# measurment_synth.net
KiCad netlist of a schematic drawn in Altium Designer
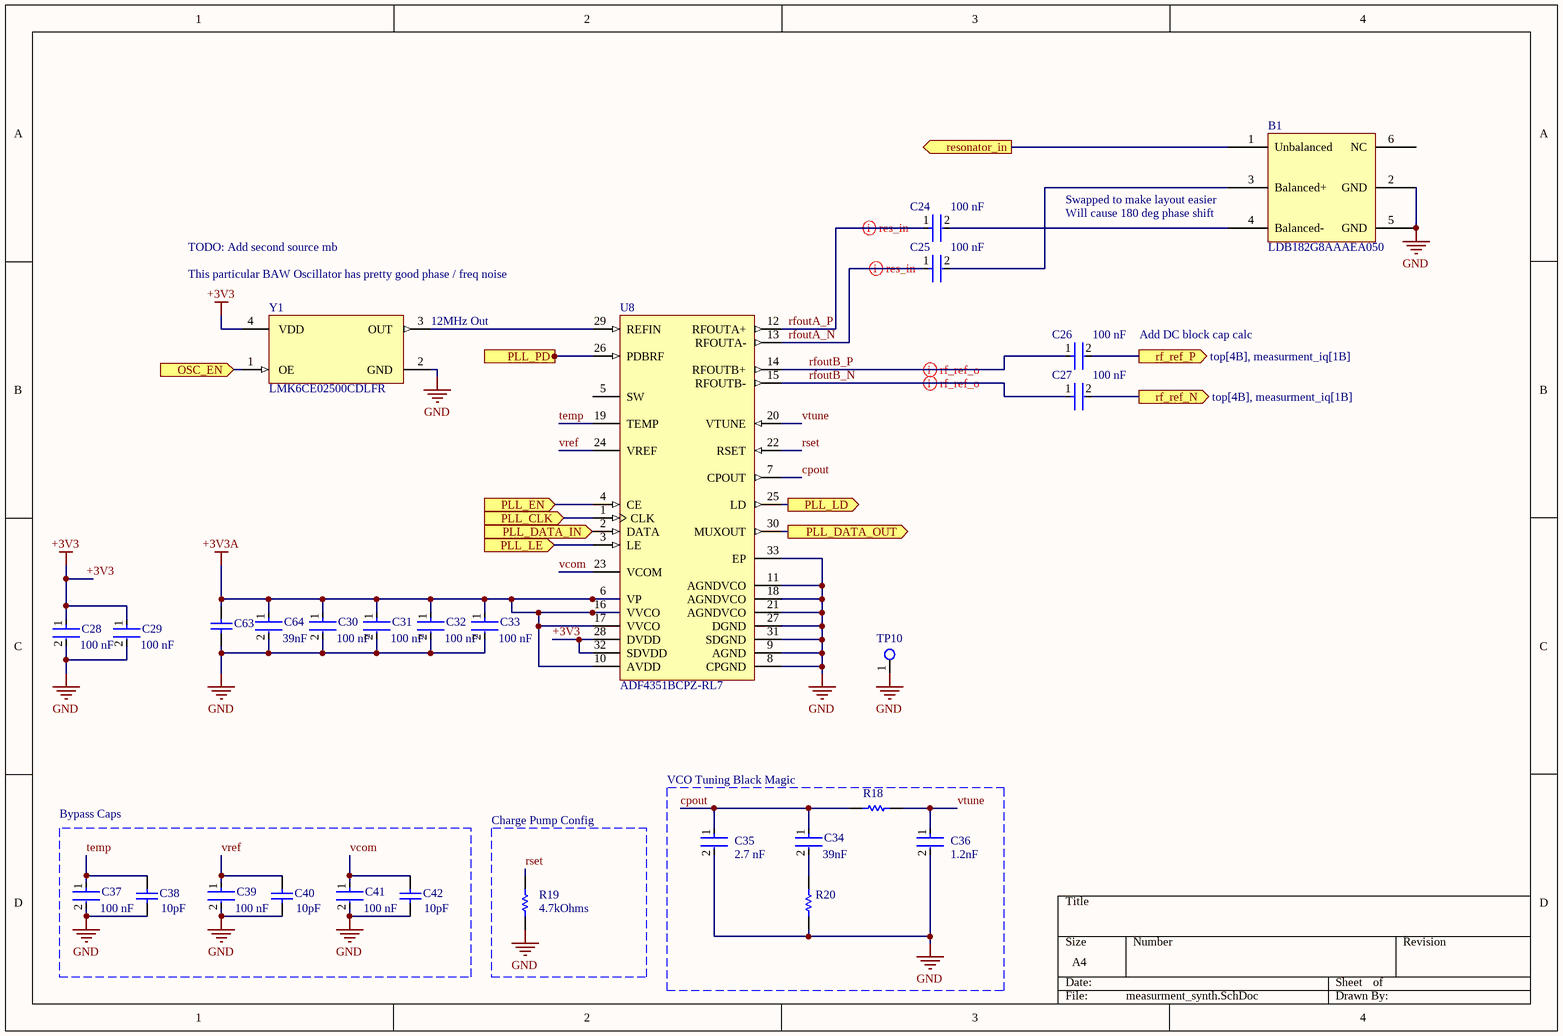
[diagram p0: measurment_synth.SchDoc]

(export (version "E")
  (design (tool "Eeschema 10.0.6"))
  (components
    (comp (ref "B1")
      (value "LDB182G8AAAEA050")
      (footprint "Balum")
      (libsource (lib "fydp") (part "LDB182G8AAAEA050"))
    )
    (comp (ref "C24")
      (value "CC0603KRX7R7BB104")
      (footprint "FP-CC0603-DA-MFG")
      (description "CAP CER 0.1UF 16V X7R 0603")
      (fields
        (field (name "OCTOPART") "https://octopart.com/cc0603krx7r7bb104-yageo-192941")
        (field (name "TOLERANCE") "0.1")
        (field (name "CAPACITANCE") "100 nF")
      )
      (libsource (lib "Altium Content Vault") (part "11868f565c42a9108669ba33697ecf6"))
    )
    (comp (ref "C25")
      (value "CC0603KRX7R7BB104")
      (footprint "FP-CC0603-DA-MFG")
      (description "CAP CER 0.1UF 16V X7R 0603")
      (fields
        (field (name "OCTOPART") "https://octopart.com/cc0603krx7r7bb104-yageo-192941")
        (field (name "TOLERANCE") "0.1")
        (field (name "CAPACITANCE") "100 nF")
      )
      (libsource (lib "Altium Content Vault") (part "11868f565c42a9108669ba33697ecf6"))
    )
    (comp (ref "C26")
      (value "CC0603KRX7R7BB104")
      (footprint "FP-CC0603-DA-MFG")
      (description "CAP CER 0.1UF 16V X7R 0603")
      (fields
        (field (name "OCTOPART") "https://octopart.com/cc0603krx7r7bb104-yageo-192941")
        (field (name "TOLERANCE") "0.1")
        (field (name "CAPACITANCE") "100 nF")
      )
      (libsource (lib "Altium Content Vault") (part "11868f565c42a9108669ba33697ecf6"))
    )
    (comp (ref "C27")
      (value "CC0603KRX7R7BB104")
      (footprint "FP-CC0603-DA-MFG")
      (description "CAP CER 0.1UF 16V X7R 0603")
      (fields
        (field (name "OCTOPART") "https://octopart.com/cc0603krx7r7bb104-yageo-192941")
        (field (name "TOLERANCE") "0.1")
        (field (name "CAPACITANCE") "100 nF")
      )
      (libsource (lib "Altium Content Vault") (part "11868f565c42a9108669ba33697ecf6"))
    )
    (comp (ref "C28")
      (value "CC0603KRX7R7BB104")
      (footprint "FP-CC0603-DA-MFG")
      (description "CAP CER 0.1UF 16V X7R 0603")
      (fields
        (field (name "OCTOPART") "https://octopart.com/cc0603krx7r7bb104-yageo-192941")
        (field (name "TOLERANCE") "0.1")
        (field (name "CAPACITANCE") "100 nF")
      )
      (libsource (lib "Altium Content Vault") (part "11868f565c42a9108669ba33697ecf6"))
    )
    (comp (ref "C29")
      (value "CC0603KRX7R7BB104")
      (footprint "FP-CC0603-DA-MFG")
      (description "CAP CER 0.1UF 16V X7R 0603")
      (fields
        (field (name "OCTOPART") "https://octopart.com/cc0603krx7r7bb104-yageo-192941")
        (field (name "TOLERANCE") "0.1")
        (field (name "CAPACITANCE") "100 nF")
      )
      (libsource (lib "Altium Content Vault") (part "11868f565c42a9108669ba33697ecf6"))
    )
    (comp (ref "C30")
      (value "CC0603KRX7R7BB104")
      (footprint "FP-CC0603-DA-MFG")
      (description "CAP CER 0.1UF 16V X7R 0603")
      (fields
        (field (name "OCTOPART") "https://octopart.com/cc0603krx7r7bb104-yageo-192941")
        (field (name "TOLERANCE") "0.1")
        (field (name "CAPACITANCE") "100 nF")
      )
      (libsource (lib "Altium Content Vault") (part "11868f565c42a9108669ba33697ecf6"))
    )
    (comp (ref "C31")
      (value "CC0603KRX7R7BB104")
      (footprint "FP-CC0603-DA-MFG")
      (description "CAP CER 0.1UF 16V X7R 0603")
      (fields
        (field (name "OCTOPART") "https://octopart.com/cc0603krx7r7bb104-yageo-192941")
        (field (name "TOLERANCE") "0.1")
        (field (name "CAPACITANCE") "100 nF")
      )
      (libsource (lib "Altium Content Vault") (part "11868f565c42a9108669ba33697ecf6"))
    )
    (comp (ref "C32")
      (value "CC0603KRX7R7BB104")
      (footprint "FP-CC0603-DA-MFG")
      (description "CAP CER 0.1UF 16V X7R 0603")
      (fields
        (field (name "OCTOPART") "https://octopart.com/cc0603krx7r7bb104-yageo-192941")
        (field (name "TOLERANCE") "0.1")
        (field (name "CAPACITANCE") "100 nF")
      )
      (libsource (lib "Altium Content Vault") (part "11868f565c42a9108669ba33697ecf6"))
    )
    (comp (ref "C33")
      (value "CC0603KRX7R7BB104")
      (footprint "FP-CC0603-DA-MFG")
      (description "CAP CER 0.1UF 16V X7R 0603")
      (fields
        (field (name "OCTOPART") "https://octopart.com/cc0603krx7r7bb104-yageo-192941")
        (field (name "TOLERANCE") "0.1")
        (field (name "CAPACITANCE") "100 nF")
      )
      (libsource (lib "Altium Content Vault") (part "11868f565c42a9108669ba33697ecf6"))
    )
    (comp (ref "C34")
      (value "GCM155R71C393KA37D")
      (footprint "FP-GCM155-0_05-IPC_B")
      (description "Ceramic Capacitor for Automotive 39nF ±10% 16VDC X7R 0402 Paper T/R")
      (fields (field (name "CAPACITANCE") "39nF") (field (name "TOLERANCE") "10%"))
      (libsource (lib "Altium Content Vault") (part "02cd4be3c70576c341d710602a673aa"))
    )
    (comp (ref "C35")
      (value "CC0402KPX7R9BB272")
      (footprint "FP-CC0402-MFG")
      (description "CC0402 2.7 nF X7R 10.00% 50 V")
      (fields
        (field (name "MANUFACTURER") "YAGEO")
        (field (name "CAPACITANCE") "2.7 nF")
        (field (name "TOLERANCE") "0.1")
      )
      (libsource (lib "Altium Content Vault") (part "11868f565c42a9108669ba33697ecf6"))
    )
    (comp (ref "C36")
      (value "GCM1885C1H122JA16J")
      (footprint "FP-GCM188-0_1-IPC_A")
      (description "Ceramic Capacitor for Automotive 1.2nF  ±5% 50VDC C0G 0603 Paper T/R")
      (fields (field (name "TOLERANCE") "5%") (field (name "CAPACITANCE") "1.2nF"))
      (libsource (lib "Altium Content Vault") (part "02cd4be3c70576c341d710602a673aa"))
    )
    (comp (ref "C37")
      (value "CC0603KRX7R7BB104")
      (footprint "FP-CC0603-DA-MFG")
      (description "CAP CER 0.1UF 16V X7R 0603")
      (fields
        (field (name "OCTOPART") "https://octopart.com/cc0603krx7r7bb104-yageo-192941")
        (field (name "TOLERANCE") "0.1")
        (field (name "CAPACITANCE") "100 nF")
      )
      (libsource (lib "Altium Content Vault") (part "11868f565c42a9108669ba33697ecf6"))
    )
    (comp (ref "C38")
      (value "CC0402JRNPO9BN100")
      (footprint "CAPC1005X55X25ML05T05")
      (description "Chip Capacitor, 10 pF, +/- 5%, 50 V, -55 to 125 degC, 0402 (1005 Metric), RoHS, Tape and Reel")
      (fields
        (field (name "TOLERANCE") "5%")
        (field (name "MANUFACTURER") "Yageo")
        (field (name "CAPACITANCE") "10pF")
      )
      (libsource (lib "Altium Content Vault") (part "CAP-NP-2"))
    )
    (comp (ref "C39")
      (value "CC0603KRX7R7BB104")
      (footprint "FP-CC0603-DA-MFG")
      (description "CAP CER 0.1UF 16V X7R 0603")
      (fields
        (field (name "OCTOPART") "https://octopart.com/cc0603krx7r7bb104-yageo-192941")
        (field (name "TOLERANCE") "0.1")
        (field (name "CAPACITANCE") "100 nF")
      )
      (libsource (lib "Altium Content Vault") (part "11868f565c42a9108669ba33697ecf6"))
    )
    (comp (ref "C40")
      (value "CC0402JRNPO9BN100")
      (footprint "CAPC1005X55X25ML05T05")
      (description "Chip Capacitor, 10 pF, +/- 5%, 50 V, -55 to 125 degC, 0402 (1005 Metric), RoHS, Tape and Reel")
      (fields
        (field (name "TOLERANCE") "5%")
        (field (name "MANUFACTURER") "Yageo")
        (field (name "CAPACITANCE") "10pF")
      )
      (libsource (lib "Altium Content Vault") (part "CAP-NP-2"))
    )
    (comp (ref "C41")
      (value "CC0603KRX7R7BB104")
      (footprint "FP-CC0603-DA-MFG")
      (description "CAP CER 0.1UF 16V X7R 0603")
      (fields
        (field (name "OCTOPART") "https://octopart.com/cc0603krx7r7bb104-yageo-192941")
        (field (name "TOLERANCE") "0.1")
        (field (name "CAPACITANCE") "100 nF")
      )
      (libsource (lib "Altium Content Vault") (part "11868f565c42a9108669ba33697ecf6"))
    )
    (comp (ref "C42")
      (value "CC0402JRNPO9BN100")
      (footprint "CAPC1005X55X25ML05T05")
      (description "Chip Capacitor, 10 pF, +/- 5%, 50 V, -55 to 125 degC, 0402 (1005 Metric), RoHS, Tape and Reel")
      (fields
        (field (name "TOLERANCE") "5%")
        (field (name "MANUFACTURER") "Yageo")
        (field (name "CAPACITANCE") "10pF")
      )
      (libsource (lib "Altium Content Vault") (part "CAP-NP-2"))
    )
    (comp (ref "C63")
      (value "GRM1555C1H270JA01D")
      (footprint "CAPC1005X55X25LL05T10")
      (fields (field (name "MANUFACTURER") "Murata"))
      (libsource (lib "Altium Content Vault") (part "CAP"))
    )
    (comp (ref "C64")
      (value "GCM155R71C393KA37D")
      (footprint "FP-GCM155-0_05-IPC_B")
      (description "Ceramic Capacitor for Automotive 39nF ±10% 16VDC X7R 0402 Paper T/R")
      (fields (field (name "CAPACITANCE") "39nF") (field (name "TOLERANCE") "10%"))
      (libsource (lib "Altium Content Vault") (part "02cd4be3c70576c341d710602a673aa"))
    )
    (comp (ref "R18")
      (value "RC0402JR-07680RL")
      (footprint "RESC1005X40X25LL05T10")
      (fields (field (name "MANUFACTURER") "Yageo / Phycomp"))
      (libsource (lib "Altium Content Vault") (part "RES"))
    )
    (comp (ref "R19")
      (value "RC0603FR-074K7L")
      (footprint "RESC1608X55X25LL10T15")
      (description "Chip Resistor, 4.7 KOhm, +/- 1%, 0.1 W, -55 to 155 degC, 0603 (1608 Metric), RoHS, Tape and Reel")
      (fields
        (field (name "MANUFACTURER") "Yageo")
        (field (name "RESISTANCE") "4.7kOhms")
        (field (name "TOLERANCE") "1%")
      )
      (libsource (lib "Altium Content Vault") (part "RES-2"))
    )
    (comp (ref "R20")
      (value "RC0603JR-07360RL")
      (footprint "RESC1608X55X25ML10T15")
      (fields (field (name "MANUFACTURER") "Yageo"))
      (libsource (lib "Altium Content Vault") (part "RES"))
    )
    (comp (ref "TP10")
      (value "Test Point")
      (footprint "test_point")
      (libsource (lib "fydp") (part "Test Point"))
    )
    (comp (ref "U8")
      (value "ADF4351BCPZ-RL7")
      (footprint "ADI-CP-32-2_L")
      (description "Wideband Synthesizer with Integrated VCO, CP-32-2, Pb-Free, 1500 Reel")
      (libsource (lib "Altium Content Vault") (part "ADI-ADF4351-CP-32-2"))
    )
    (comp (ref "Y1")
      (value "LMK6CE02500CDLFR")
      (footprint "DLF0004A_MFG")
      (description "\"LOW-JITTER, HIGH-PERFORMANCE, BU\" 25 MHz LVCMOS Oscillator 1.8V Enable/Disable 4-VDFN")
      (libsource (lib "Altium Content Vault") (part "b2b2c4fa024628cfd4920a92de059ff"))
    )
  )
  (nets
    (net (code "1") (name "+3V3") (class "Default")
      (node (ref "C28") (pin "1") (pinfunction "1_1") (pintype "passive"))
      (node (ref "C29") (pin "1") (pinfunction "1_1") (pintype "passive"))
      (node (ref "U8") (pin "28") (pinfunction "DVDD_28") (pintype "power_in"))
      (node (ref "U8") (pin "32") (pinfunction "SDVDD_32") (pintype "power_in"))
      (node (ref "Y1") (pin "4") (pinfunction "VDD_4") (pintype "power_in"))
    )
    (net (code "2") (name "+3V3A") (class "Default")
      (node (ref "C30") (pin "1") (pinfunction "1_1") (pintype "passive"))
      (node (ref "C31") (pin "1") (pinfunction "1_1") (pintype "passive"))
      (node (ref "C32") (pin "1") (pinfunction "1_1") (pintype "passive"))
      (node (ref "C33") (pin "1") (pinfunction "1_1") (pintype "passive"))
      (node (ref "C63") (pin "2") (pinfunction "2_2") (pintype "passive"))
      (node (ref "C64") (pin "1") (pinfunction "1_1") (pintype "passive"))
      (node (ref "U8") (pin "10") (pinfunction "AVDD_10") (pintype "power_in"))
      (node (ref "U8") (pin "16") (pinfunction "VVCO_16") (pintype "power_in"))
      (node (ref "U8") (pin "17") (pinfunction "VVCO_17") (pintype "power_in"))
      (node (ref "U8") (pin "6") (pinfunction "VP_6") (pintype "power_in"))
    )
    (net (code "3") (name "/OSC_EN") (class "Default")
      (node (ref "Y1") (pin "1") (pinfunction "OE_1") (pintype "input"))
    )
    (net (code "4") (name "/PLL_CLK") (class "Default")
      (node (ref "U8") (pin "1") (pinfunction "CLK_1") (pintype "input"))
    )
    (net (code "5") (name "/PLL_DATA_IN") (class "Default")
      (node (ref "U8") (pin "2") (pinfunction "DATA_2") (pintype "input"))
    )
    (net (code "6") (name "/PLL_DATA_OUT") (class "Default")
      (node (ref "U8") (pin "30") (pinfunction "MUXOUT_30") (pintype "output"))
    )
    (net (code "7") (name "/PLL_EN") (class "Default")
      (node (ref "U8") (pin "4") (pinfunction "CE_4") (pintype "input"))
    )
    (net (code "8") (name "/PLL_LD") (class "Default")
      (node (ref "U8") (pin "25") (pinfunction "LD_25") (pintype "output"))
    )
    (net (code "9") (name "/PLL_LE") (class "Default")
      (node (ref "U8") (pin "3") (pinfunction "LE_3") (pintype "input"))
    )
    (net (code "10") (name "/PLL_PD") (class "Default")
      (node (ref "U8") (pin "26") (pinfunction "PDBRF_26") (pintype "input"))
    )
    (net (code "11") (name "/cpout") (class "Default")
      (node (ref "C34") (pin "1") (pinfunction "1_1") (pintype "passive"))
      (node (ref "C35") (pin "1") (pinfunction "1_1") (pintype "passive"))
      (node (ref "R18") (pin "1") (pinfunction "1_1") (pintype "passive"))
      (node (ref "U8") (pin "7") (pinfunction "CPOUT_7") (pintype "output"))
    )
    (net (code "12") (name "/resonator_in") (class "Default")
      (node (ref "B1") (pin "1") (pinfunction "Unbalanced_1") (pintype "passive"))
    )
    (net (code "13") (name "/rf_ref_N") (class "Default")
      (node (ref "C27") (pin "2") (pinfunction "2_2") (pintype "passive"))
    )
    (net (code "14") (name "/rf_ref_P") (class "Default")
      (node (ref "C26") (pin "2") (pinfunction "2_2") (pintype "passive"))
    )
    (net (code "15") (name "/rfoutA_N") (class "Default")
      (node (ref "C25") (pin "1") (pinfunction "1_1") (pintype "passive"))
      (node (ref "U8") (pin "13") (pinfunction "RFOUTA-_13") (pintype "output"))
    )
    (net (code "16") (name "/rfoutA_P") (class "Default")
      (node (ref "C24") (pin "1") (pinfunction "1_1") (pintype "passive"))
      (node (ref "U8") (pin "12") (pinfunction "RFOUTA+_12") (pintype "output"))
    )
    (net (code "17") (name "/rfoutB_N") (class "Default")
      (node (ref "C27") (pin "1") (pinfunction "1_1") (pintype "passive"))
      (node (ref "U8") (pin "15") (pinfunction "RFOUTB-_15") (pintype "output"))
    )
    (net (code "18") (name "/rfoutB_P") (class "Default")
      (node (ref "C26") (pin "1") (pinfunction "1_1") (pintype "passive"))
      (node (ref "U8") (pin "14") (pinfunction "RFOUTB+_14") (pintype "output"))
    )
    (net (code "19") (name "/rset") (class "Default")
      (node (ref "R19") (pin "2") (pinfunction "2_2") (pintype "passive"))
      (node (ref "U8") (pin "22") (pinfunction "RSET_22") (pintype "input"))
    )
    (net (code "20") (name "/temp") (class "Default")
      (node (ref "C37") (pin "1") (pinfunction "1_1") (pintype "passive"))
      (node (ref "C38") (pin "2") (pinfunction "2_2") (pintype "passive"))
      (node (ref "U8") (pin "19") (pinfunction "TEMP_19") (pintype "passive"))
    )
    (net (code "21") (name "/vcom") (class "Default")
      (node (ref "C41") (pin "1") (pinfunction "1_1") (pintype "passive"))
      (node (ref "C42") (pin "2") (pinfunction "2_2") (pintype "passive"))
      (node (ref "U8") (pin "23") (pinfunction "VCOM_23") (pintype "passive"))
    )
    (net (code "22") (name "/vref") (class "Default")
      (node (ref "C39") (pin "1") (pinfunction "1_1") (pintype "passive"))
      (node (ref "C40") (pin "2") (pinfunction "2_2") (pintype "passive"))
      (node (ref "U8") (pin "24") (pinfunction "VREF_24") (pintype "passive"))
    )
    (net (code "23") (name "/vtune") (class "Default")
      (node (ref "C36") (pin "1") (pinfunction "1_1") (pintype "passive"))
      (node (ref "R18") (pin "2") (pinfunction "2_2") (pintype "passive"))
      (node (ref "U8") (pin "20") (pinfunction "VTUNE_20") (pintype "input"))
    )
    (net (code "24") (name "GND") (class "Default")
      (node (ref "B1") (pin "2") (pinfunction "GND_2") (pintype "passive"))
      (node (ref "B1") (pin "5") (pinfunction "GND_5") (pintype "passive"))
      (node (ref "C28") (pin "2") (pinfunction "2_2") (pintype "passive"))
      (node (ref "C29") (pin "2") (pinfunction "2_2") (pintype "passive"))
      (node (ref "C30") (pin "2") (pinfunction "2_2") (pintype "passive"))
      (node (ref "C31") (pin "2") (pinfunction "2_2") (pintype "passive"))
      (node (ref "C32") (pin "2") (pinfunction "2_2") (pintype "passive"))
      (node (ref "C33") (pin "2") (pinfunction "2_2") (pintype "passive"))
      (node (ref "C35") (pin "2") (pinfunction "2_2") (pintype "passive"))
      (node (ref "C36") (pin "2") (pinfunction "2_2") (pintype "passive"))
      (node (ref "C37") (pin "2") (pinfunction "2_2") (pintype "passive"))
      (node (ref "C38") (pin "1") (pinfunction "1_1") (pintype "passive"))
      (node (ref "C39") (pin "2") (pinfunction "2_2") (pintype "passive"))
      (node (ref "C40") (pin "1") (pinfunction "1_1") (pintype "passive"))
      (node (ref "C41") (pin "2") (pinfunction "2_2") (pintype "passive"))
      (node (ref "C42") (pin "1") (pinfunction "1_1") (pintype "passive"))
      (node (ref "C63") (pin "1") (pinfunction "1_1") (pintype "passive"))
      (node (ref "C64") (pin "2") (pinfunction "2_2") (pintype "passive"))
      (node (ref "R19") (pin "1") (pinfunction "1_1") (pintype "passive"))
      (node (ref "R20") (pin "1") (pinfunction "1_1") (pintype "passive"))
      (node (ref "TP10") (pin "1") (pintype "passive"))
      (node (ref "U8") (pin "11") (pinfunction "AGNDVCO_11") (pintype "power_in"))
      (node (ref "U8") (pin "18") (pinfunction "AGNDVCO_18") (pintype "power_in"))
      (node (ref "U8") (pin "21") (pinfunction "AGNDVCO_21") (pintype "power_in"))
      (node (ref "U8") (pin "27") (pinfunction "DGND_27") (pintype "power_in"))
      (node (ref "U8") (pin "31") (pinfunction "SDGND_31") (pintype "power_in"))
      (node (ref "U8") (pin "33") (pinfunction "EP_33") (pintype "power_in"))
      (node (ref "U8") (pin "8") (pinfunction "CPGND_8") (pintype "power_in"))
      (node (ref "U8") (pin "9") (pinfunction "AGND_9") (pintype "power_in"))
      (node (ref "Y1") (pin "2") (pinfunction "GND_2") (pintype "power_in"))
    )
    (net (code "25") (name "Net-(B1-Balanced+)") (class "Default")
      (node (ref "B1") (pin "3") (pinfunction "Balanced+_3") (pintype "passive"))
      (node (ref "C25") (pin "2") (pinfunction "2_2") (pintype "passive"))
    )
    (net (code "26") (name "Net-(B1-Balanced-)") (class "Default")
      (node (ref "B1") (pin "4") (pinfunction "Balanced-_4") (pintype "passive"))
      (node (ref "C24") (pin "2") (pinfunction "2_2") (pintype "passive"))
    )
    (net (code "27") (name "Net-(C34-Pad2)") (class "Default")
      (node (ref "C34") (pin "2") (pinfunction "2_2") (pintype "passive"))
      (node (ref "R20") (pin "2") (pinfunction "2_2") (pintype "passive"))
    )
    (net (code "28") (name "Net-(U8-REFIN)") (class "Default")
      (node (ref "U8") (pin "29") (pinfunction "REFIN_29") (pintype "input"))
      (node (ref "Y1") (pin "3") (pinfunction "OUT_3") (pintype "output"))
    )
    (net (code "29") (name "unconnected-(B1-NC-Pad6)") (class "Default")
      (node (ref "B1") (pin "6") (pinfunction "NC_6") (pintype "passive"))
    )
    (net (code "30") (name "unconnected-(U8-SW-Pad5)") (class "Default")
      (node (ref "U8") (pin "5") (pinfunction "SW_5") (pintype "passive"))
    )
  )
)
